# vixen1.net
KiCad netlist of a schematic drawn in EAGLE
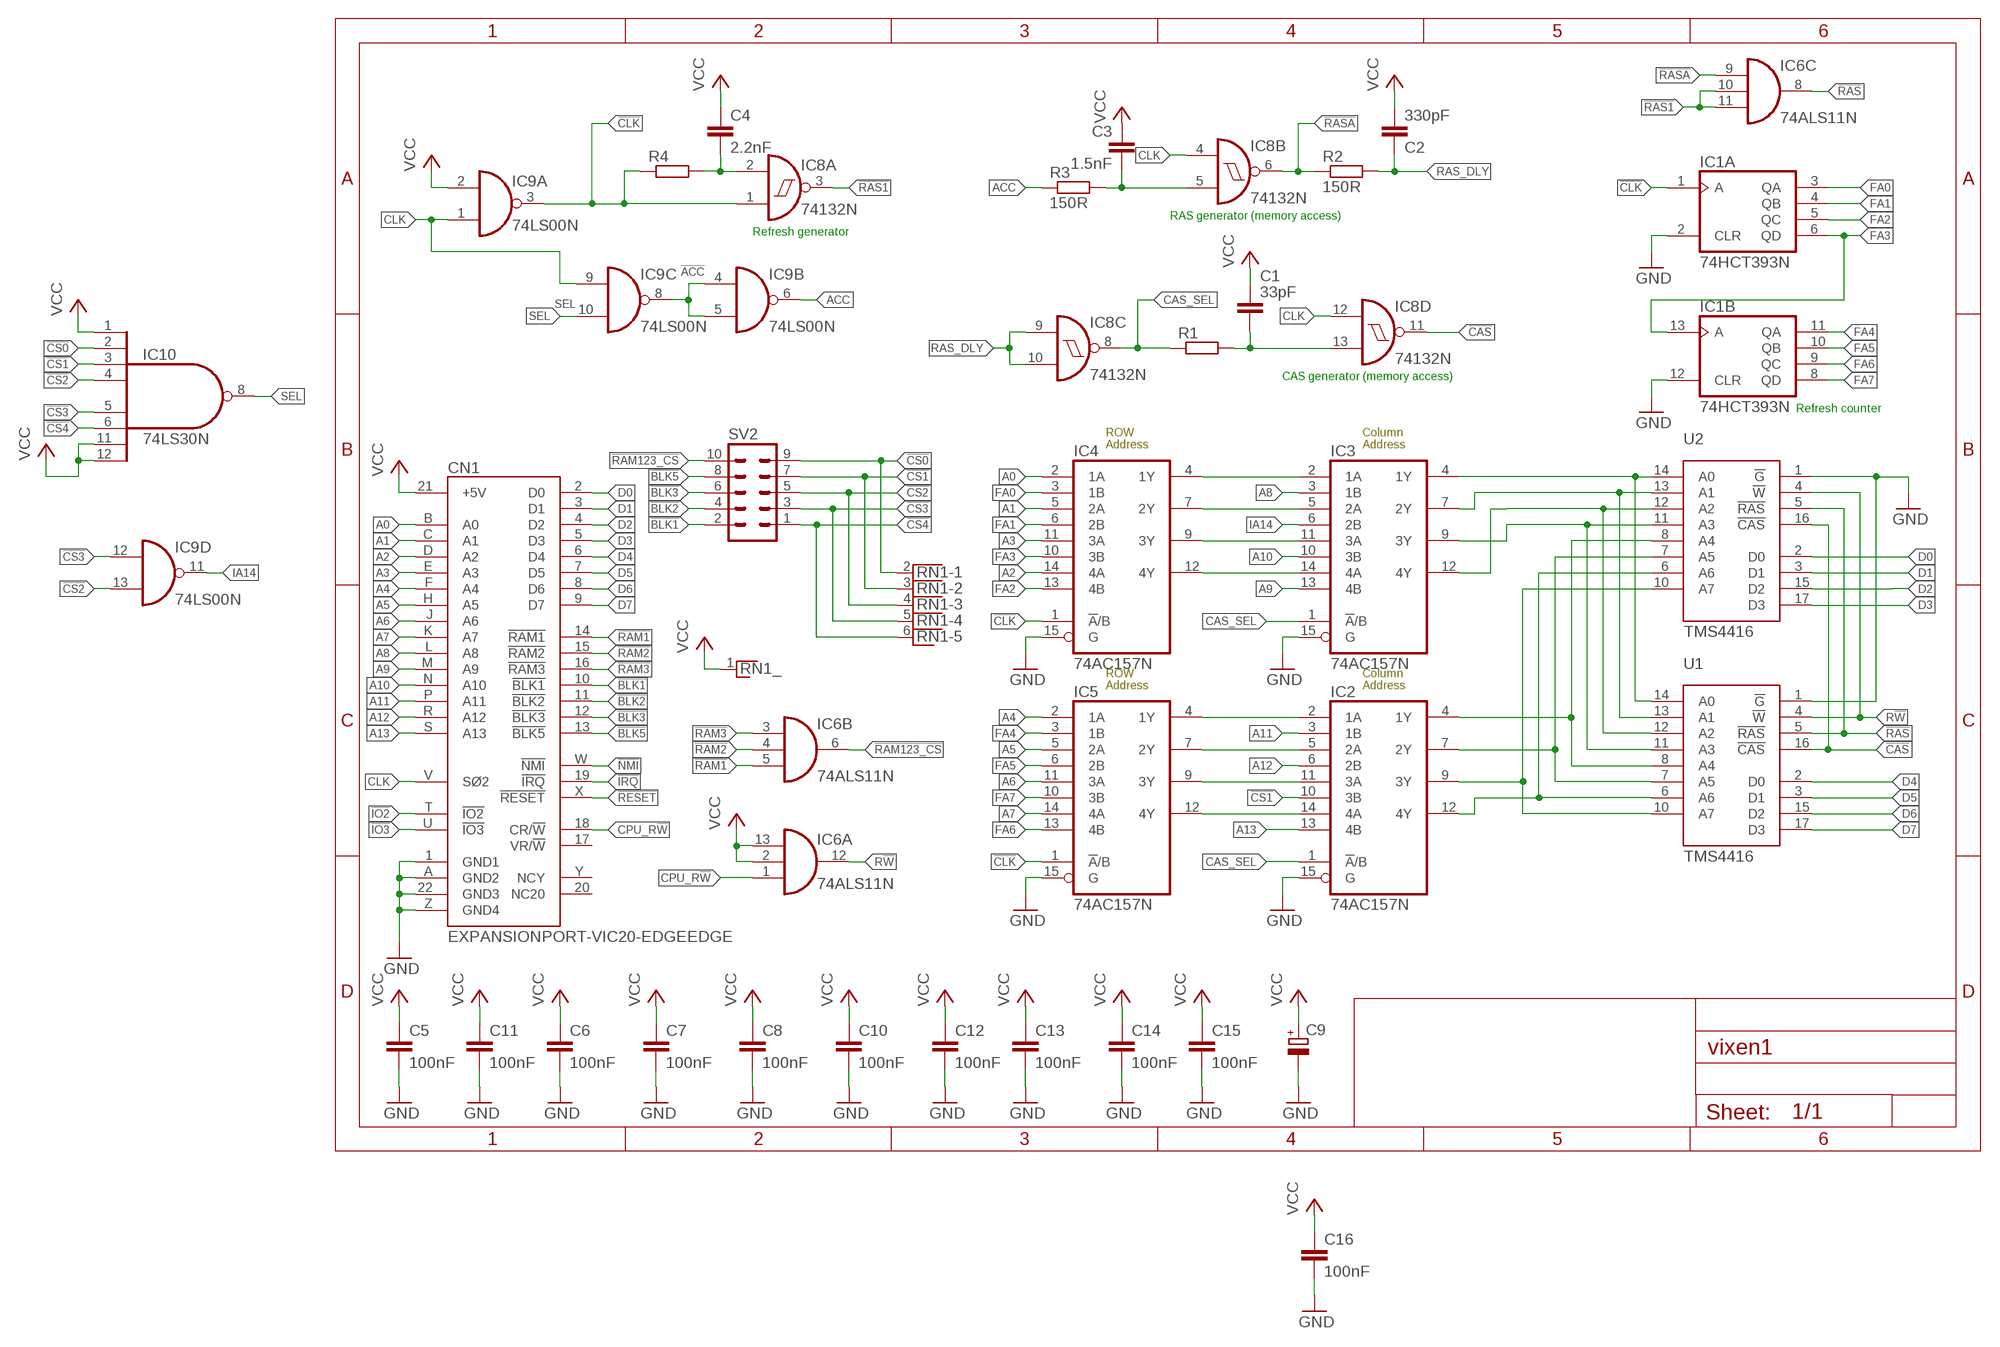
[diagram p0: schematic, sheet 1]

(export (version "E")
  (design (tool "Eeschema 10.0.6"))
  (components
    (comp (ref "C1")
      (value "33pF")
      (footprint "eagle-import:C025-025X050")
      (libsource (lib "eagle-import") (part "C-EU025-025X050"))
    )
    (comp (ref "C2")
      (value "330pF")
      (footprint "eagle-import:C025-025X050")
      (libsource (lib "eagle-import") (part "C-EU025-025X050"))
    )
    (comp (ref "C3")
      (value "1.5nF")
      (footprint "eagle-import:C025-025X050")
      (libsource (lib "eagle-import") (part "C-EU025-025X050"))
    )
    (comp (ref "C4")
      (value "2.2nF")
      (footprint "eagle-import:C025-025X050")
      (libsource (lib "eagle-import") (part "C-EU025-025X050"))
    )
    (comp (ref "C5")
      (value "100nF")
      (footprint "eagle-import:C025-025X050")
      (libsource (lib "eagle-import") (part "C-EU025-025X050"))
    )
    (comp (ref "C6")
      (value "100nF")
      (footprint "eagle-import:C025-025X050")
      (libsource (lib "eagle-import") (part "C-EU025-025X050"))
    )
    (comp (ref "C7")
      (value "100nF")
      (footprint "eagle-import:C025-025X050")
      (libsource (lib "eagle-import") (part "C-EU025-025X050"))
    )
    (comp (ref "C8")
      (value "100nF")
      (footprint "eagle-import:C025-025X050")
      (libsource (lib "eagle-import") (part "C-EU025-025X050"))
    )
    (comp (ref "C9")
      (value "CPOL-EUE15-5AXIAL")
      (footprint "eagle-import:E15-5")
      (libsource (lib "eagle-import") (part "CPOL-EUE15-5AXIAL"))
    )
    (comp (ref "C10")
      (value "100nF")
      (footprint "eagle-import:C025-025X050")
      (libsource (lib "eagle-import") (part "C-EU025-025X050"))
    )
    (comp (ref "C11")
      (value "100nF")
      (footprint "eagle-import:C025-025X050")
      (libsource (lib "eagle-import") (part "C-EU025-025X050"))
    )
    (comp (ref "C12")
      (value "100nF")
      (footprint "eagle-import:C025-025X050")
      (libsource (lib "eagle-import") (part "C-EU025-025X050"))
    )
    (comp (ref "C13")
      (value "100nF")
      (footprint "eagle-import:C025-025X050")
      (libsource (lib "eagle-import") (part "C-EU025-025X050"))
    )
    (comp (ref "C14")
      (value "100nF")
      (footprint "eagle-import:C025-025X050")
      (libsource (lib "eagle-import") (part "C-EU025-025X050"))
    )
    (comp (ref "C15")
      (value "100nF")
      (footprint "eagle-import:C025-025X050")
      (libsource (lib "eagle-import") (part "C-EU025-025X050"))
    )
    (comp (ref "C16")
      (value "100nF")
      (footprint "eagle-import:C025-025X050")
      (libsource (lib "eagle-import") (part "C-EU025-025X050"))
    )
    (comp (ref "CN1")
      (value "EXPANSIONPORT-VIC20-EDGEEDGE")
      (footprint "eagle-import:UPS44EDGE")
      (libsource (lib "eagle-import") (part "EXPANSIONPORT-VIC20-EDGEEDGE"))
    )
    (comp (ref "IC1")
      (value "74HCT393N")
      (footprint "eagle-import:DIL14")
      (libsource (lib "eagle-import") (part "74393NHCT"))
    )
    (comp (ref "IC2")
      (value "74AC157N")
      (footprint "eagle-import:DIL16")
      (libsource (lib "eagle-import") (part "74157NAC"))
    )
    (comp (ref "IC3")
      (value "74AC157N")
      (footprint "eagle-import:DIL16")
      (libsource (lib "eagle-import") (part "74157NAC"))
    )
    (comp (ref "IC4")
      (value "74AC157N")
      (footprint "eagle-import:DIL16")
      (libsource (lib "eagle-import") (part "74157NAC"))
    )
    (comp (ref "IC5")
      (value "74AC157N")
      (footprint "eagle-import:DIL16")
      (libsource (lib "eagle-import") (part "74157NAC"))
    )
    (comp (ref "IC6")
      (value "74ALS11N")
      (footprint "eagle-import:DIL14")
      (libsource (lib "eagle-import") (part "7411NALS"))
    )
    (comp (ref "IC8")
      (value "74132N")
      (footprint "eagle-import:DIL14")
      (libsource (lib "eagle-import") (part "74132N"))
    )
    (comp (ref "IC9")
      (value "74LS00N")
      (footprint "eagle-import:DIL14")
      (libsource (lib "eagle-import") (part "7400NLS"))
    )
    (comp (ref "IC10")
      (value "74LS30N")
      (footprint "eagle-import:DIL14")
      (libsource (lib "eagle-import") (part "7430NLS"))
    )
    (comp (ref "R1")
      (value "R-EU_0204/7")
      (footprint "eagle-import:0204_7")
      (libsource (lib "eagle-import") (part "R-EU_0204/7"))
    )
    (comp (ref "R2")
      (value "150R")
      (footprint "eagle-import:0204_7")
      (libsource (lib "eagle-import") (part "R-EU_0204/7"))
    )
    (comp (ref "R3")
      (value "150R")
      (footprint "eagle-import:0204_7")
      (libsource (lib "eagle-import") (part "R-EU_0204/7"))
    )
    (comp (ref "R4")
      (value "R-EU_0204/7")
      (footprint "eagle-import:0204_7")
      (libsource (lib "eagle-import") (part "R-EU_0204/7"))
    )
    (comp (ref "RN1")
      (value "RNX5")
      (footprint "eagle-import:RN-6")
      (libsource (lib "eagle-import") (part "RNX5"))
    )
    (comp (ref "SV2")
      (value "MA05-2")
      (footprint "eagle-import:MA05-2")
      (libsource (lib "eagle-import") (part "MA05-2"))
    )
    (comp (ref "U1")
      (value "TMS4416")
      (footprint "eagle-import:DIL18")
      (libsource (lib "eagle-import") (part "TMS4416"))
    )
    (comp (ref "U2")
      (value "TMS4416")
      (footprint "eagle-import:DIL18")
      (libsource (lib "eagle-import") (part "TMS4416"))
    )
  )
  (nets
    (net (code "1") (name "/CPU_R~{W}") (class "Default")
      (node (ref "CN1") (pin "18") (pinfunction "CR/~{W}_18") (pintype "output"))
      (node (ref "IC6") (pin "1") (pinfunction "I0_1") (pintype "input"))
    )
    (net (code "2") (name "/R~{W}") (class "Default")
      (node (ref "IC6") (pin "12") (pinfunction "O_12") (pintype "output"))
      (node (ref "U1") (pin "4") (pinfunction "~{W}_4") (pintype "bidirectional"))
      (node (ref "U2") (pin "4") (pinfunction "~{W}_4") (pintype "bidirectional"))
    )
    (net (code "3") (name "/~{ACC}") (class "Default")
      (node (ref "IC9") (pin "4") (pinfunction "I0_4") (pintype "input"))
      (node (ref "IC9") (pin "5") (pinfunction "I1_5") (pintype "input"))
      (node (ref "IC9") (pin "8") (pinfunction "O_8") (pintype "output"))
    )
    (net (code "4") (name "/~{BLK1}") (class "Default")
      (node (ref "CN1") (pin "10") (pinfunction "~{BLK1}_10") (pintype "output"))
      (node (ref "SV2") (pin "2") (pinfunction "2_2") (pintype "passive"))
    )
    (net (code "5") (name "/~{BLK2}") (class "Default")
      (node (ref "CN1") (pin "11") (pinfunction "~{BLK2}_11") (pintype "output"))
      (node (ref "SV2") (pin "4") (pinfunction "4_4") (pintype "passive"))
    )
    (net (code "6") (name "/~{BLK3}") (class "Default")
      (node (ref "CN1") (pin "12") (pinfunction "~{BLK3}_12") (pintype "output"))
      (node (ref "SV2") (pin "6") (pinfunction "6_6") (pintype "passive"))
    )
    (net (code "7") (name "/~{BLK5}") (class "Default")
      (node (ref "CN1") (pin "13") (pinfunction "~{BLK5}_13") (pintype "output"))
      (node (ref "SV2") (pin "8") (pinfunction "8_8") (pintype "passive"))
    )
    (net (code "8") (name "/~{CAS}") (class "Default")
      (node (ref "IC8") (pin "11") (pinfunction "O_11") (pintype "output"))
      (node (ref "U1") (pin "16") (pinfunction "~{CAS}_16") (pintype "bidirectional"))
      (node (ref "U2") (pin "16") (pinfunction "~{CAS}_16") (pintype "bidirectional"))
    )
    (net (code "9") (name "/~{CLK}") (class "Default")
      (node (ref "IC1") (pin "1") (pinfunction "A_1") (pintype "input"))
      (node (ref "IC4") (pin "1") (pinfunction "~{A}/B_1") (pintype "input"))
      (node (ref "IC5") (pin "1") (pinfunction "~{A}/B_1") (pintype "input"))
      (node (ref "IC8") (pin "1") (pinfunction "I0_1") (pintype "input"))
      (node (ref "IC9") (pin "3") (pinfunction "O_3") (pintype "output"))
      (node (ref "R4") (pin "1") (pinfunction "1_1") (pintype "passive"))
    )
    (net (code "10") (name "/~{CS0}") (class "Default")
      (node (ref "IC10") (pin "2") (pinfunction "I1_2") (pintype "input"))
      (node (ref "RN1") (pin "2") (pinfunction "1_2") (pintype "passive"))
      (node (ref "SV2") (pin "9") (pinfunction "9_9") (pintype "passive"))
    )
    (net (code "11") (name "/~{CS1}") (class "Default")
      (node (ref "IC10") (pin "3") (pinfunction "I2_3") (pintype "input"))
      (node (ref "IC2") (pin "10") (pinfunction "3B_10") (pintype "input"))
      (node (ref "RN1") (pin "3") (pinfunction "1_3") (pintype "passive"))
      (node (ref "SV2") (pin "7") (pinfunction "7_7") (pintype "passive"))
    )
    (net (code "12") (name "/~{CS2}") (class "Default")
      (node (ref "IC10") (pin "4") (pinfunction "I3_4") (pintype "input"))
      (node (ref "IC9") (pin "13") (pinfunction "I1_13") (pintype "input"))
      (node (ref "RN1") (pin "4") (pinfunction "1_4") (pintype "passive"))
      (node (ref "SV2") (pin "5") (pinfunction "5_5") (pintype "passive"))
    )
    (net (code "13") (name "/~{CS3}") (class "Default")
      (node (ref "IC10") (pin "5") (pinfunction "I4_5") (pintype "input"))
      (node (ref "IC9") (pin "12") (pinfunction "I0_12") (pintype "input"))
      (node (ref "RN1") (pin "5") (pinfunction "1_5") (pintype "passive"))
      (node (ref "SV2") (pin "3") (pinfunction "3_3") (pintype "passive"))
    )
    (net (code "14") (name "/~{CS4}") (class "Default")
      (node (ref "IC10") (pin "6") (pinfunction "I5_6") (pintype "input"))
      (node (ref "RN1") (pin "6") (pinfunction "1_6") (pintype "passive"))
      (node (ref "SV2") (pin "1") (pinfunction "1_1") (pintype "passive"))
    )
    (net (code "15") (name "/~{IO2}") (class "Default")
      (node (ref "CN1") (pin "T") (pinfunction "~{IO2}_T") (pintype "output"))
    )
    (net (code "16") (name "/~{IO3}") (class "Default")
      (node (ref "CN1") (pin "U") (pinfunction "~{IO3}_U") (pintype "output"))
    )
    (net (code "17") (name "/~{IRQ}") (class "Default")
      (node (ref "CN1") (pin "19") (pinfunction "~{IRQ}_19") (pintype "bidirectional"))
    )
    (net (code "18") (name "/~{NMI}") (class "Default")
      (node (ref "CN1") (pin "W") (pinfunction "~{NMI}_W") (pintype "bidirectional"))
    )
    (net (code "19") (name "/~{RAM1}") (class "Default")
      (node (ref "CN1") (pin "14") (pinfunction "~{RAM1}_14") (pintype "output"))
      (node (ref "IC6") (pin "5") (pinfunction "I2_5") (pintype "input"))
    )
    (net (code "20") (name "/~{RAM2}") (class "Default")
      (node (ref "CN1") (pin "15") (pinfunction "~{RAM2}_15") (pintype "output"))
      (node (ref "IC6") (pin "4") (pinfunction "I1_4") (pintype "input"))
    )
    (net (code "21") (name "/~{RAM3}") (class "Default")
      (node (ref "CN1") (pin "16") (pinfunction "~{RAM3}_16") (pintype "output"))
      (node (ref "IC6") (pin "3") (pinfunction "I0_3") (pintype "input"))
    )
    (net (code "22") (name "/~{RAM123_CS}") (class "Default")
      (node (ref "IC6") (pin "6") (pinfunction "O_6") (pintype "output"))
      (node (ref "SV2") (pin "10") (pinfunction "10_10") (pintype "passive"))
    )
    (net (code "23") (name "/~{RAS1}") (class "Default")
      (node (ref "IC6") (pin "10") (pinfunction "I1_10") (pintype "input"))
      (node (ref "IC6") (pin "11") (pinfunction "I2_11") (pintype "input"))
      (node (ref "IC8") (pin "3") (pinfunction "O_3") (pintype "output"))
    )
    (net (code "24") (name "/~{RASA}") (class "Default")
      (node (ref "IC6") (pin "9") (pinfunction "I0_9") (pintype "input"))
      (node (ref "IC8") (pin "6") (pinfunction "O_6") (pintype "output"))
      (node (ref "R2") (pin "1") (pinfunction "1_1") (pintype "passive"))
    )
    (net (code "25") (name "/~{RAS}") (class "Default")
      (node (ref "IC6") (pin "8") (pinfunction "O_8") (pintype "output"))
      (node (ref "U1") (pin "5") (pinfunction "~{RAS}_5") (pintype "bidirectional"))
      (node (ref "U2") (pin "5") (pinfunction "~{RAS}_5") (pintype "bidirectional"))
    )
    (net (code "26") (name "/~{RESET}") (class "Default")
      (node (ref "CN1") (pin "X") (pinfunction "~{RESET}_X") (pintype "bidirectional"))
    )
    (net (code "27") (name "A0") (class "Default")
      (node (ref "CN1") (pin "B") (pinfunction "A0_B") (pintype "output"))
      (node (ref "IC4") (pin "2") (pinfunction "1A_2") (pintype "input"))
    )
    (net (code "28") (name "A1") (class "Default")
      (node (ref "CN1") (pin "C") (pinfunction "A1_C") (pintype "output"))
      (node (ref "IC4") (pin "5") (pinfunction "2A_5") (pintype "input"))
    )
    (net (code "29") (name "A2") (class "Default")
      (node (ref "CN1") (pin "D") (pinfunction "A2_D") (pintype "output"))
      (node (ref "IC4") (pin "14") (pinfunction "4A_14") (pintype "input"))
    )
    (net (code "30") (name "A3") (class "Default")
      (node (ref "CN1") (pin "E") (pinfunction "A3_E") (pintype "output"))
      (node (ref "IC4") (pin "11") (pinfunction "3A_11") (pintype "input"))
    )
    (net (code "31") (name "A4") (class "Default")
      (node (ref "CN1") (pin "F") (pinfunction "A4_F") (pintype "output"))
      (node (ref "IC5") (pin "2") (pinfunction "1A_2") (pintype "input"))
    )
    (net (code "32") (name "A5") (class "Default")
      (node (ref "CN1") (pin "H") (pinfunction "A5_H") (pintype "output"))
      (node (ref "IC5") (pin "5") (pinfunction "2A_5") (pintype "input"))
    )
    (net (code "33") (name "A6") (class "Default")
      (node (ref "CN1") (pin "J") (pinfunction "A6_J") (pintype "output"))
      (node (ref "IC5") (pin "11") (pinfunction "3A_11") (pintype "input"))
    )
    (net (code "34") (name "A7") (class "Default")
      (node (ref "CN1") (pin "K") (pinfunction "A7_K") (pintype "output"))
      (node (ref "IC5") (pin "14") (pinfunction "4A_14") (pintype "input"))
    )
    (net (code "35") (name "A8") (class "Default")
      (node (ref "CN1") (pin "L") (pinfunction "A8_L") (pintype "output"))
      (node (ref "IC3") (pin "3") (pinfunction "1B_3") (pintype "input"))
    )
    (net (code "36") (name "A9") (class "Default")
      (node (ref "CN1") (pin "M") (pinfunction "A9_M") (pintype "output"))
      (node (ref "IC3") (pin "13") (pinfunction "4B_13") (pintype "input"))
    )
    (net (code "37") (name "A10") (class "Default")
      (node (ref "CN1") (pin "N") (pinfunction "A10_N") (pintype "output"))
      (node (ref "IC3") (pin "10") (pinfunction "3B_10") (pintype "input"))
    )
    (net (code "38") (name "A11") (class "Default")
      (node (ref "CN1") (pin "P") (pinfunction "A11_P") (pintype "output"))
      (node (ref "IC2") (pin "3") (pinfunction "1B_3") (pintype "input"))
    )
    (net (code "39") (name "A12") (class "Default")
      (node (ref "CN1") (pin "R") (pinfunction "A12_R") (pintype "output"))
      (node (ref "IC2") (pin "6") (pinfunction "2B_6") (pintype "input"))
    )
    (net (code "40") (name "A13") (class "Default")
      (node (ref "CN1") (pin "S") (pinfunction "A13_S") (pintype "output"))
      (node (ref "IC2") (pin "13") (pinfunction "4B_13") (pintype "input"))
    )
    (net (code "41") (name "ACC") (class "Default")
      (node (ref "IC9") (pin "6") (pinfunction "O_6") (pintype "output"))
      (node (ref "R3") (pin "1") (pinfunction "1_1") (pintype "passive"))
    )
    (net (code "42") (name "CAS_SEL") (class "Default")
      (node (ref "IC2") (pin "1") (pinfunction "~{A}/B_1") (pintype "input"))
      (node (ref "IC3") (pin "1") (pinfunction "~{A}/B_1") (pintype "input"))
      (node (ref "IC8") (pin "8") (pinfunction "O_8") (pintype "output"))
      (node (ref "R1") (pin "1") (pinfunction "1_1") (pintype "passive"))
    )
    (net (code "43") (name "CLK") (class "Default")
      (node (ref "CN1") (pin "V") (pinfunction "SØ2_V") (pintype "output"))
      (node (ref "IC8") (pin "12") (pinfunction "I0_12") (pintype "input"))
      (node (ref "IC8") (pin "4") (pinfunction "I0_4") (pintype "input"))
      (node (ref "IC9") (pin "1") (pinfunction "I0_1") (pintype "input"))
      (node (ref "IC9") (pin "9") (pinfunction "I0_9") (pintype "input"))
    )
    (net (code "44") (name "D0") (class "Default")
      (node (ref "CN1") (pin "2") (pinfunction "D0_2") (pintype "bidirectional"))
      (node (ref "U2") (pin "2") (pinfunction "D0_2") (pintype "bidirectional"))
    )
    (net (code "45") (name "D1") (class "Default")
      (node (ref "CN1") (pin "3") (pinfunction "D1_3") (pintype "bidirectional"))
      (node (ref "U2") (pin "3") (pinfunction "D1_3") (pintype "bidirectional"))
    )
    (net (code "46") (name "D2") (class "Default")
      (node (ref "CN1") (pin "4") (pinfunction "D2_4") (pintype "bidirectional"))
      (node (ref "U2") (pin "15") (pinfunction "D2_15") (pintype "bidirectional"))
    )
    (net (code "47") (name "D3") (class "Default")
      (node (ref "CN1") (pin "5") (pinfunction "D3_5") (pintype "bidirectional"))
      (node (ref "U2") (pin "17") (pinfunction "D3_17") (pintype "bidirectional"))
    )
    (net (code "48") (name "D4") (class "Default")
      (node (ref "CN1") (pin "6") (pinfunction "D4_6") (pintype "bidirectional"))
      (node (ref "U1") (pin "2") (pinfunction "D0_2") (pintype "bidirectional"))
    )
    (net (code "49") (name "D5") (class "Default")
      (node (ref "CN1") (pin "7") (pinfunction "D5_7") (pintype "bidirectional"))
      (node (ref "U1") (pin "3") (pinfunction "D1_3") (pintype "bidirectional"))
    )
    (net (code "50") (name "D6") (class "Default")
      (node (ref "CN1") (pin "8") (pinfunction "D6_8") (pintype "bidirectional"))
      (node (ref "U1") (pin "15") (pinfunction "D2_15") (pintype "bidirectional"))
    )
    (net (code "51") (name "D7") (class "Default")
      (node (ref "CN1") (pin "9") (pinfunction "D7_9") (pintype "bidirectional"))
      (node (ref "U1") (pin "17") (pinfunction "D3_17") (pintype "bidirectional"))
    )
    (net (code "52") (name "FA0") (class "Default")
      (node (ref "IC1") (pin "3") (pinfunction "QA_3") (pintype "output"))
      (node (ref "IC4") (pin "3") (pinfunction "1B_3") (pintype "input"))
    )
    (net (code "53") (name "FA1") (class "Default")
      (node (ref "IC1") (pin "4") (pinfunction "QB_4") (pintype "output"))
      (node (ref "IC4") (pin "6") (pinfunction "2B_6") (pintype "input"))
    )
    (net (code "54") (name "FA2") (class "Default")
      (node (ref "IC1") (pin "5") (pinfunction "QC_5") (pintype "output"))
      (node (ref "IC4") (pin "13") (pinfunction "4B_13") (pintype "input"))
    )
    (net (code "55") (name "FA3") (class "Default")
      (node (ref "IC1") (pin "13") (pinfunction "A_13") (pintype "input"))
      (node (ref "IC1") (pin "6") (pinfunction "QD_6") (pintype "output"))
      (node (ref "IC4") (pin "10") (pinfunction "3B_10") (pintype "input"))
    )
    (net (code "56") (name "FA4") (class "Default")
      (node (ref "IC1") (pin "11") (pinfunction "QA_11") (pintype "output"))
      (node (ref "IC5") (pin "3") (pinfunction "1B_3") (pintype "input"))
    )
    (net (code "57") (name "FA5") (class "Default")
      (node (ref "IC1") (pin "10") (pinfunction "QB_10") (pintype "output"))
      (node (ref "IC5") (pin "6") (pinfunction "2B_6") (pintype "input"))
    )
    (net (code "58") (name "FA6") (class "Default")
      (node (ref "IC1") (pin "9") (pinfunction "QC_9") (pintype "output"))
      (node (ref "IC5") (pin "13") (pinfunction "4B_13") (pintype "input"))
    )
    (net (code "59") (name "FA7") (class "Default")
      (node (ref "IC1") (pin "8") (pinfunction "QD_8") (pintype "output"))
      (node (ref "IC5") (pin "10") (pinfunction "3B_10") (pintype "input"))
    )
    (net (code "60") (name "GND") (class "Default")
      (node (ref "C10") (pin "2") (pinfunction "2_2") (pintype "passive"))
      (node (ref "C11") (pin "2") (pinfunction "2_2") (pintype "passive"))
      (node (ref "C12") (pin "2") (pinfunction "2_2") (pintype "passive"))
      (node (ref "C13") (pin "2") (pinfunction "2_2") (pintype "passive"))
      (node (ref "C14") (pin "2") (pinfunction "2_2") (pintype "passive"))
      (node (ref "C15") (pin "2") (pinfunction "2_2") (pintype "passive"))
      (node (ref "C16") (pin "2") (pinfunction "2_2") (pintype "passive"))
      (node (ref "C5") (pin "2") (pinfunction "2_2") (pintype "passive"))
      (node (ref "C6") (pin "2") (pinfunction "2_2") (pintype "passive"))
      (node (ref "C7") (pin "2") (pinfunction "2_2") (pintype "passive"))
      (node (ref "C8") (pin "2") (pinfunction "2_2") (pintype "passive"))
      (node (ref "C9") (pin "-") (pinfunction "-_-") (pintype "passive"))
      (node (ref "CN1") (pin "1") (pinfunction "GND1_1") (pintype "passive"))
      (node (ref "CN1") (pin "22") (pinfunction "GND3_22") (pintype "passive"))
      (node (ref "CN1") (pin "A") (pinfunction "GND2_A") (pintype "passive"))
      (node (ref "CN1") (pin "Z") (pinfunction "GND4_Z") (pintype "passive"))
      (node (ref "IC1") (pin "12") (pinfunction "CLR_12") (pintype "input"))
      (node (ref "IC1") (pin "2") (pinfunction "CLR_2") (pintype "input"))
      (node (ref "IC2") (pin "15") (pinfunction "G_15") (pintype "input"))
      (node (ref "IC3") (pin "15") (pinfunction "G_15") (pintype "input"))
      (node (ref "IC4") (pin "15") (pinfunction "G_15") (pintype "input"))
      (node (ref "IC5") (pin "15") (pinfunction "G_15") (pintype "input"))
      (node (ref "U1") (pin "1") (pinfunction "~{G}_1") (pintype "bidirectional"))
      (node (ref "U2") (pin "1") (pinfunction "~{G}_1") (pintype "bidirectional"))
    )
    (net (code "61") (name "IA14") (class "Default")
      (node (ref "IC3") (pin "6") (pinfunction "2B_6") (pintype "input"))
      (node (ref "IC9") (pin "11") (pinfunction "O_11") (pintype "output"))
    )
    (net (code "62") (name "Net-(IC2A-1A)") (class "Default")
      (node (ref "IC2") (pin "2") (pinfunction "1A_2") (pintype "input"))
      (node (ref "IC5") (pin "4") (pinfunction "1Y_4") (pintype "output"))
    )
    (net (code "63") (name "Net-(IC2A-1Y)") (class "Default")
      (node (ref "IC2") (pin "4") (pinfunction "1Y_4") (pintype "output"))
      (node (ref "U1") (pin "8") (pinfunction "A4_8") (pintype "input"))
      (node (ref "U2") (pin "8") (pinfunction "A4_8") (pintype "input"))
    )
    (net (code "64") (name "Net-(IC2A-2A)") (class "Default")
      (node (ref "IC2") (pin "5") (pinfunction "2A_5") (pintype "input"))
      (node (ref "IC5") (pin "7") (pinfunction "2Y_7") (pintype "output"))
    )
    (net (code "65") (name "Net-(IC2A-2Y)") (class "Default")
      (node (ref "IC2") (pin "7") (pinfunction "2Y_7") (pintype "output"))
      (node (ref "U1") (pin "7") (pinfunction "A5_7") (pintype "input"))
      (node (ref "U2") (pin "7") (pinfunction "A5_7") (pintype "input"))
    )
    (net (code "66") (name "Net-(IC2A-3A)") (class "Default")
      (node (ref "IC2") (pin "11") (pinfunction "3A_11") (pintype "input"))
      (node (ref "IC5") (pin "9") (pinfunction "3Y_9") (pintype "output"))
    )
    (net (code "67") (name "Net-(IC2A-3Y)") (class "Default")
      (node (ref "IC2") (pin "9") (pinfunction "3Y_9") (pintype "output"))
      (node (ref "U1") (pin "10") (pinfunction "A7_10") (pintype "input"))
      (node (ref "U2") (pin "10") (pinfunction "A7_10") (pintype "input"))
    )
    (net (code "68") (name "Net-(IC2A-4A)") (class "Default")
      (node (ref "IC2") (pin "14") (pinfunction "4A_14") (pintype "input"))
      (node (ref "IC5") (pin "12") (pinfunction "4Y_12") (pintype "output"))
    )
    (net (code "69") (name "Net-(IC2A-4Y)") (class "Default")
      (node (ref "IC2") (pin "12") (pinfunction "4Y_12") (pintype "output"))
      (node (ref "U1") (pin "6") (pinfunction "A6_6") (pintype "input"))
      (node (ref "U2") (pin "6") (pinfunction "A6_6") (pintype "input"))
    )
    (net (code "70") (name "Net-(IC3A-1A)") (class "Default")
      (node (ref "IC3") (pin "2") (pinfunction "1A_2") (pintype "input"))
      (node (ref "IC4") (pin "4") (pinfunction "1Y_4") (pintype "output"))
    )
    (net (code "71") (name "Net-(IC3A-1Y)") (class "Default")
      (node (ref "IC3") (pin "4") (pinfunction "1Y_4") (pintype "output"))
      (node (ref "U1") (pin "14") (pinfunction "A0_14") (pintype "input"))
      (node (ref "U2") (pin "14") (pinfunction "A0_14") (pintype "input"))
    )
    (net (code "72") (name "Net-(IC3A-2A)") (class "Default")
      (node (ref "IC3") (pin "5") (pinfunction "2A_5") (pintype "input"))
      (node (ref "IC4") (pin "7") (pinfunction "2Y_7") (pintype "output"))
    )
    (net (code "73") (name "Net-(IC3A-2Y)") (class "Default")
      (node (ref "IC3") (pin "7") (pinfunction "2Y_7") (pintype "output"))
      (node (ref "U1") (pin "13") (pinfunction "A1_13") (pintype "input"))
      (node (ref "U2") (pin "13") (pinfunction "A1_13") (pintype "input"))
    )
    (net (code "74") (name "Net-(IC3A-3A)") (class "Default")
      (node (ref "IC3") (pin "11") (pinfunction "3A_11") (pintype "input"))
      (node (ref "IC4") (pin "9") (pinfunction "3Y_9") (pintype "output"))
    )
    (net (code "75") (name "Net-(IC3A-3Y)") (class "Default")
      (node (ref "IC3") (pin "9") (pinfunction "3Y_9") (pintype "output"))
      (node (ref "U1") (pin "11") (pinfunction "A3_11") (pintype "input"))
      (node (ref "U2") (pin "11") (pinfunction "A3_11") (pintype "input"))
    )
    (net (code "76") (name "Net-(IC3A-4A)") (class "Default")
      (node (ref "IC3") (pin "14") (pinfunction "4A_14") (pintype "input"))
      (node (ref "IC4") (pin "12") (pinfunction "4Y_12") (pintype "output"))
    )
    (net (code "77") (name "Net-(IC3A-4Y)") (class "Default")
      (node (ref "IC3") (pin "12") (pinfunction "4Y_12") (pintype "output"))
      (node (ref "U1") (pin "12") (pinfunction "A2_12") (pintype "input"))
      (node (ref "U2") (pin "12") (pinfunction "A2_12") (pintype "input"))
    )
    (net (code "78") (name "Net-(IC8A-I1)") (class "Default")
      (node (ref "C4") (pin "2") (pinfunction "2_2") (pintype "passive"))
      (node (ref "IC8") (pin "2") (pinfunction "I1_2") (pintype "input"))
      (node (ref "R4") (pin "2") (pinfunction "2_2") (pintype "passive"))
    )
    (net (code "79") (name "Net-(IC8B-I1)") (class "Default")
      (node (ref "C3") (pin "2") (pinfunction "2_2") (pintype "passive"))
      (node (ref "IC8") (pin "5") (pinfunction "I1_5") (pintype "input"))
      (node (ref "R3") (pin "2") (pinfunction "2_2") (pintype "passive"))
    )
    (net (code "80") (name "Net-(IC8D-I1)") (class "Default")
      (node (ref "C1") (pin "2") (pinfunction "2_2") (pintype "passive"))
      (node (ref "IC8") (pin "13") (pinfunction "I1_13") (pintype "input"))
      (node (ref "R1") (pin "2") (pinfunction "2_2") (pintype "passive"))
    )
    (net (code "81") (name "RAS_DLY") (class "Default")
      (node (ref "C2") (pin "1") (pinfunction "1_1") (pintype "passive"))
      (node (ref "IC8") (pin "10") (pinfunction "I1_10") (pintype "input"))
      (node (ref "IC8") (pin "9") (pinfunction "I0_9") (pintype "input"))
      (node (ref "R2") (pin "2") (pinfunction "2_2") (pintype "passive"))
    )
    (net (code "82") (name "SEL") (class "Default")
      (node (ref "IC10") (pin "8") (pinfunction "O_8") (pintype "output"))
      (node (ref "IC9") (pin "10") (pinfunction "I1_10") (pintype "input"))
    )
    (net (code "83") (name "VCC") (class "Default")
      (node (ref "C1") (pin "1") (pinfunction "1_1") (pintype "passive"))
      (node (ref "C10") (pin "1") (pinfunction "1_1") (pintype "passive"))
      (node (ref "C11") (pin "1") (pinfunction "1_1") (pintype "passive"))
      (node (ref "C12") (pin "1") (pinfunction "1_1") (pintype "passive"))
      (node (ref "C13") (pin "1") (pinfunction "1_1") (pintype "passive"))
      (node (ref "C14") (pin "1") (pinfunction "1_1") (pintype "passive"))
      (node (ref "C15") (pin "1") (pinfunction "1_1") (pintype "passive"))
      (node (ref "C16") (pin "1") (pinfunction "1_1") (pintype "passive"))
      (node (ref "C2") (pin "2") (pinfunction "2_2") (pintype "passive"))
      (node (ref "C3") (pin "1") (pinfunction "1_1") (pintype "passive"))
      (node (ref "C4") (pin "1") (pinfunction "1_1") (pintype "passive"))
      (node (ref "C5") (pin "1") (pinfunction "1_1") (pintype "passive"))
      (node (ref "C6") (pin "1") (pinfunction "1_1") (pintype "passive"))
      (node (ref "C7") (pin "1") (pinfunction "1_1") (pintype "passive"))
      (node (ref "C8") (pin "1") (pinfunction "1_1") (pintype "passive"))
      (node (ref "C9") (pin "+") (pinfunction "+_+") (pintype "passive"))
      (node (ref "CN1") (pin "21") (pinfunction "+5V_21") (pintype "power_in"))
      (node (ref "IC10") (pin "1") (pinfunction "I0_1") (pintype "input"))
      (node (ref "IC10") (pin "11") (pinfunction "I6_11") (pintype "input"))
      (node (ref "IC10") (pin "12") (pinfunction "I7_12") (pintype "input"))
      (node (ref "IC6") (pin "13") (pinfunction "I2_13") (pintype "input"))
      (node (ref "IC6") (pin "2") (pinfunction "I1_2") (pintype "input"))
      (node (ref "IC9") (pin "2") (pinfunction "I1_2") (pintype "input"))
      (node (ref "RN1") (pin "1") (pinfunction "1_1") (pintype "passive"))
    )
    (net (code "84") (name "unconnected-(CN1-NC20-Pad20)") (class "Default")
      (node (ref "CN1") (pin "20") (pinfunction "NC20_20") (pintype "passive"))
    )
    (net (code "85") (name "unconnected-(CN1-NCY-PadY)") (class "Default")
      (node (ref "CN1") (pin "Y") (pinfunction "NCY_Y") (pintype "passive"))
    )
    (net (code "86") (name "unconnected-(CN1-VR{slash}~{W}-Pad17)") (class "Default")
      (node (ref "CN1") (pin "17") (pinfunction "VR/~{W}_17") (pintype "output"))
    )
  )
)
